# Bidirectional_Voltage_Translator.net
KiCad netlist of a schematic drawn in Altium Designer
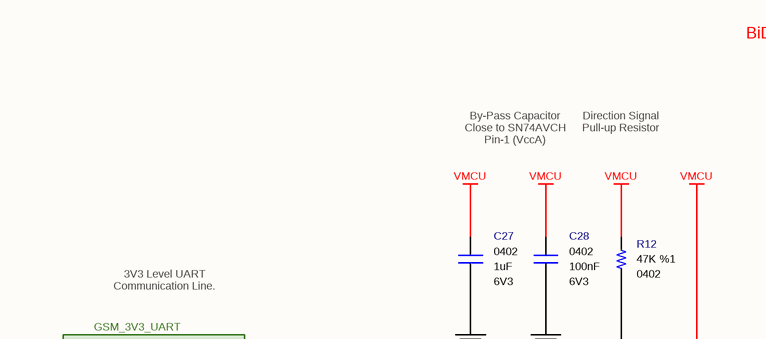
[diagram p0: Bidirectional Voltage Translator.SchDoc, top left]
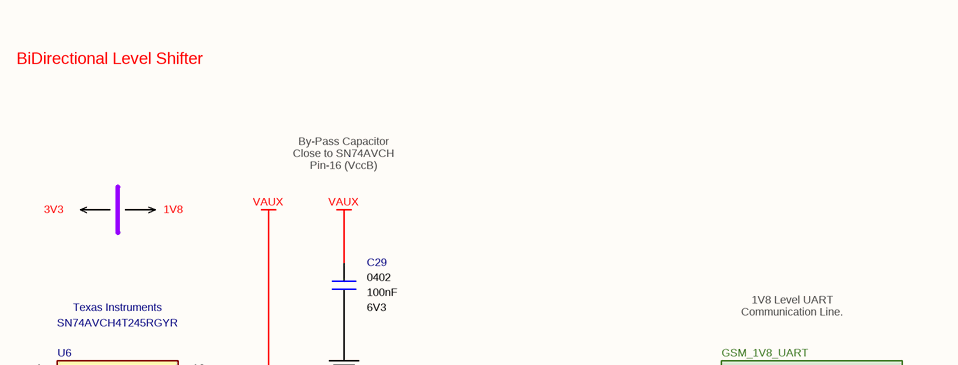
[diagram p1: Bidirectional Voltage Translator.SchDoc, top right]
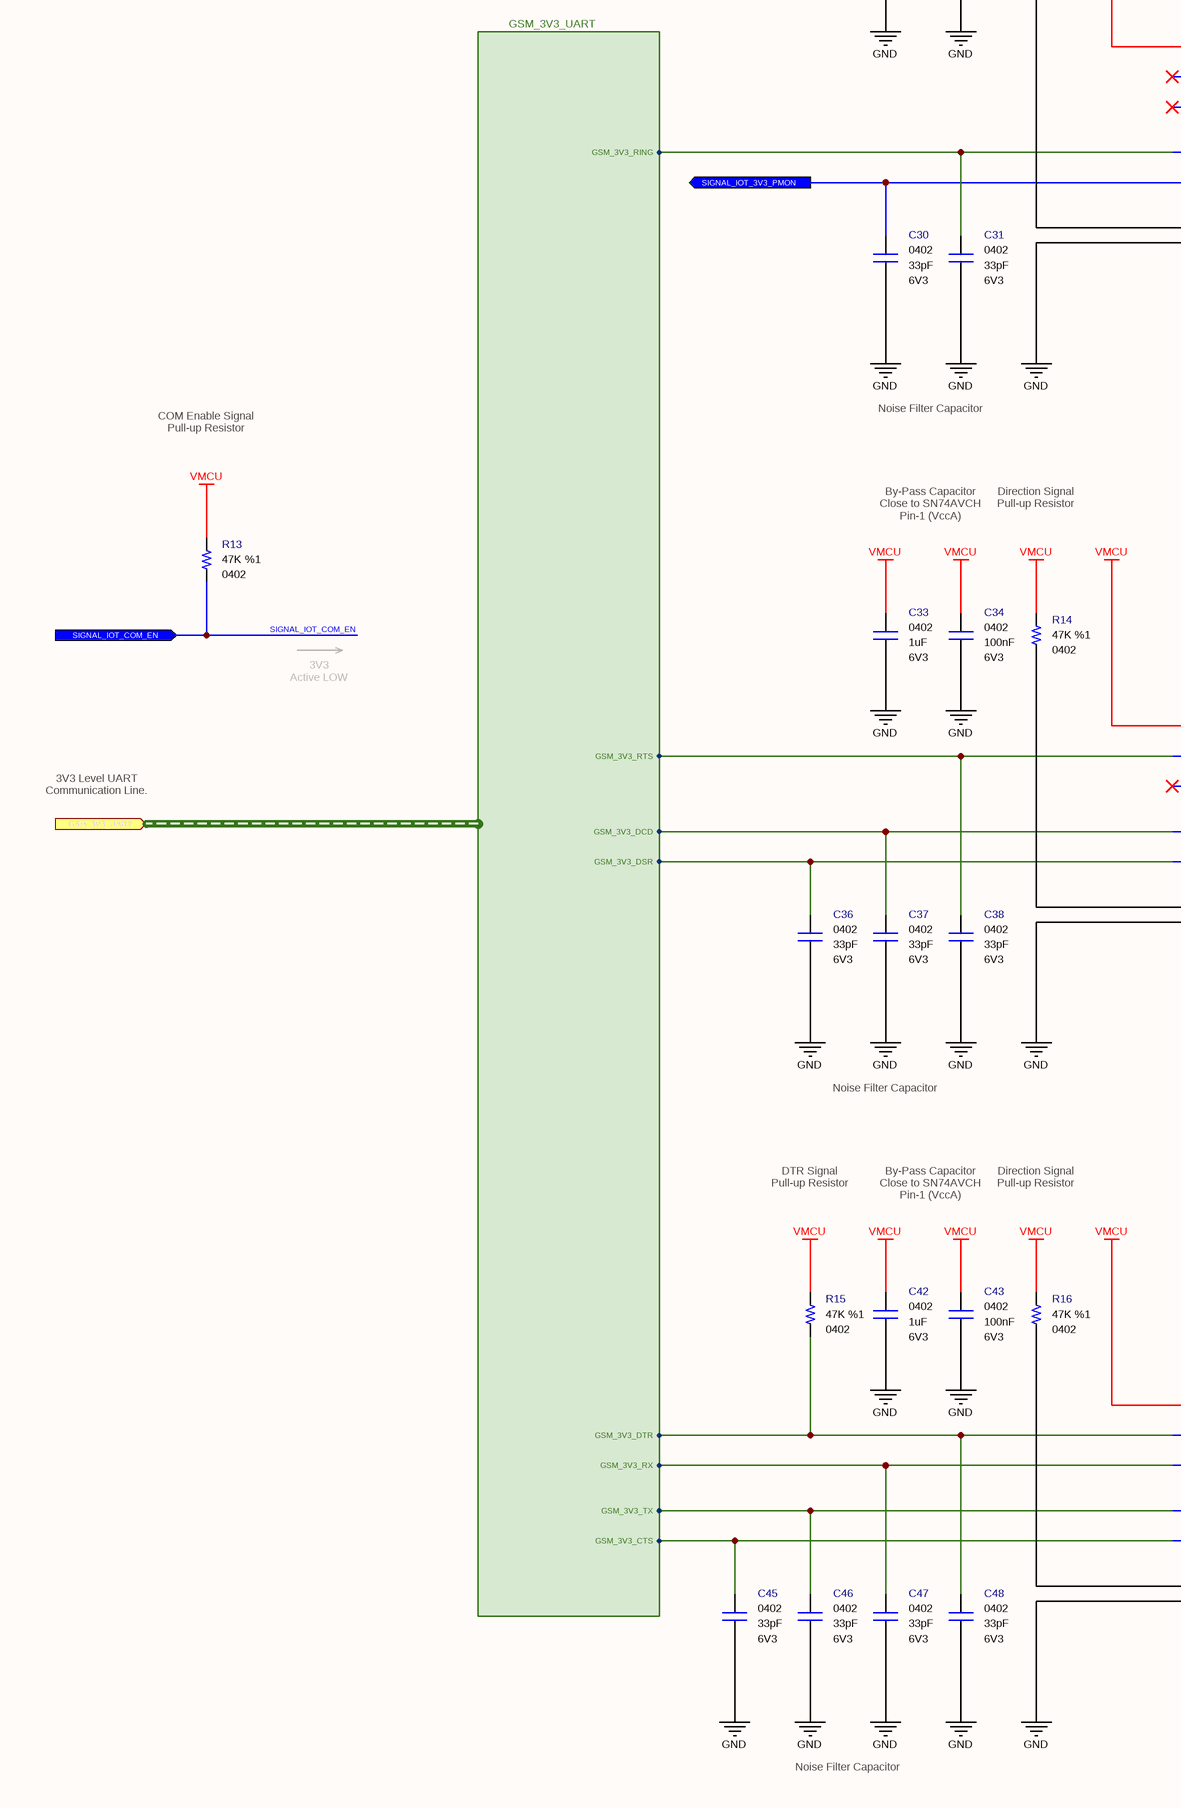
[diagram p2: Bidirectional Voltage Translator.SchDoc, bottom left]
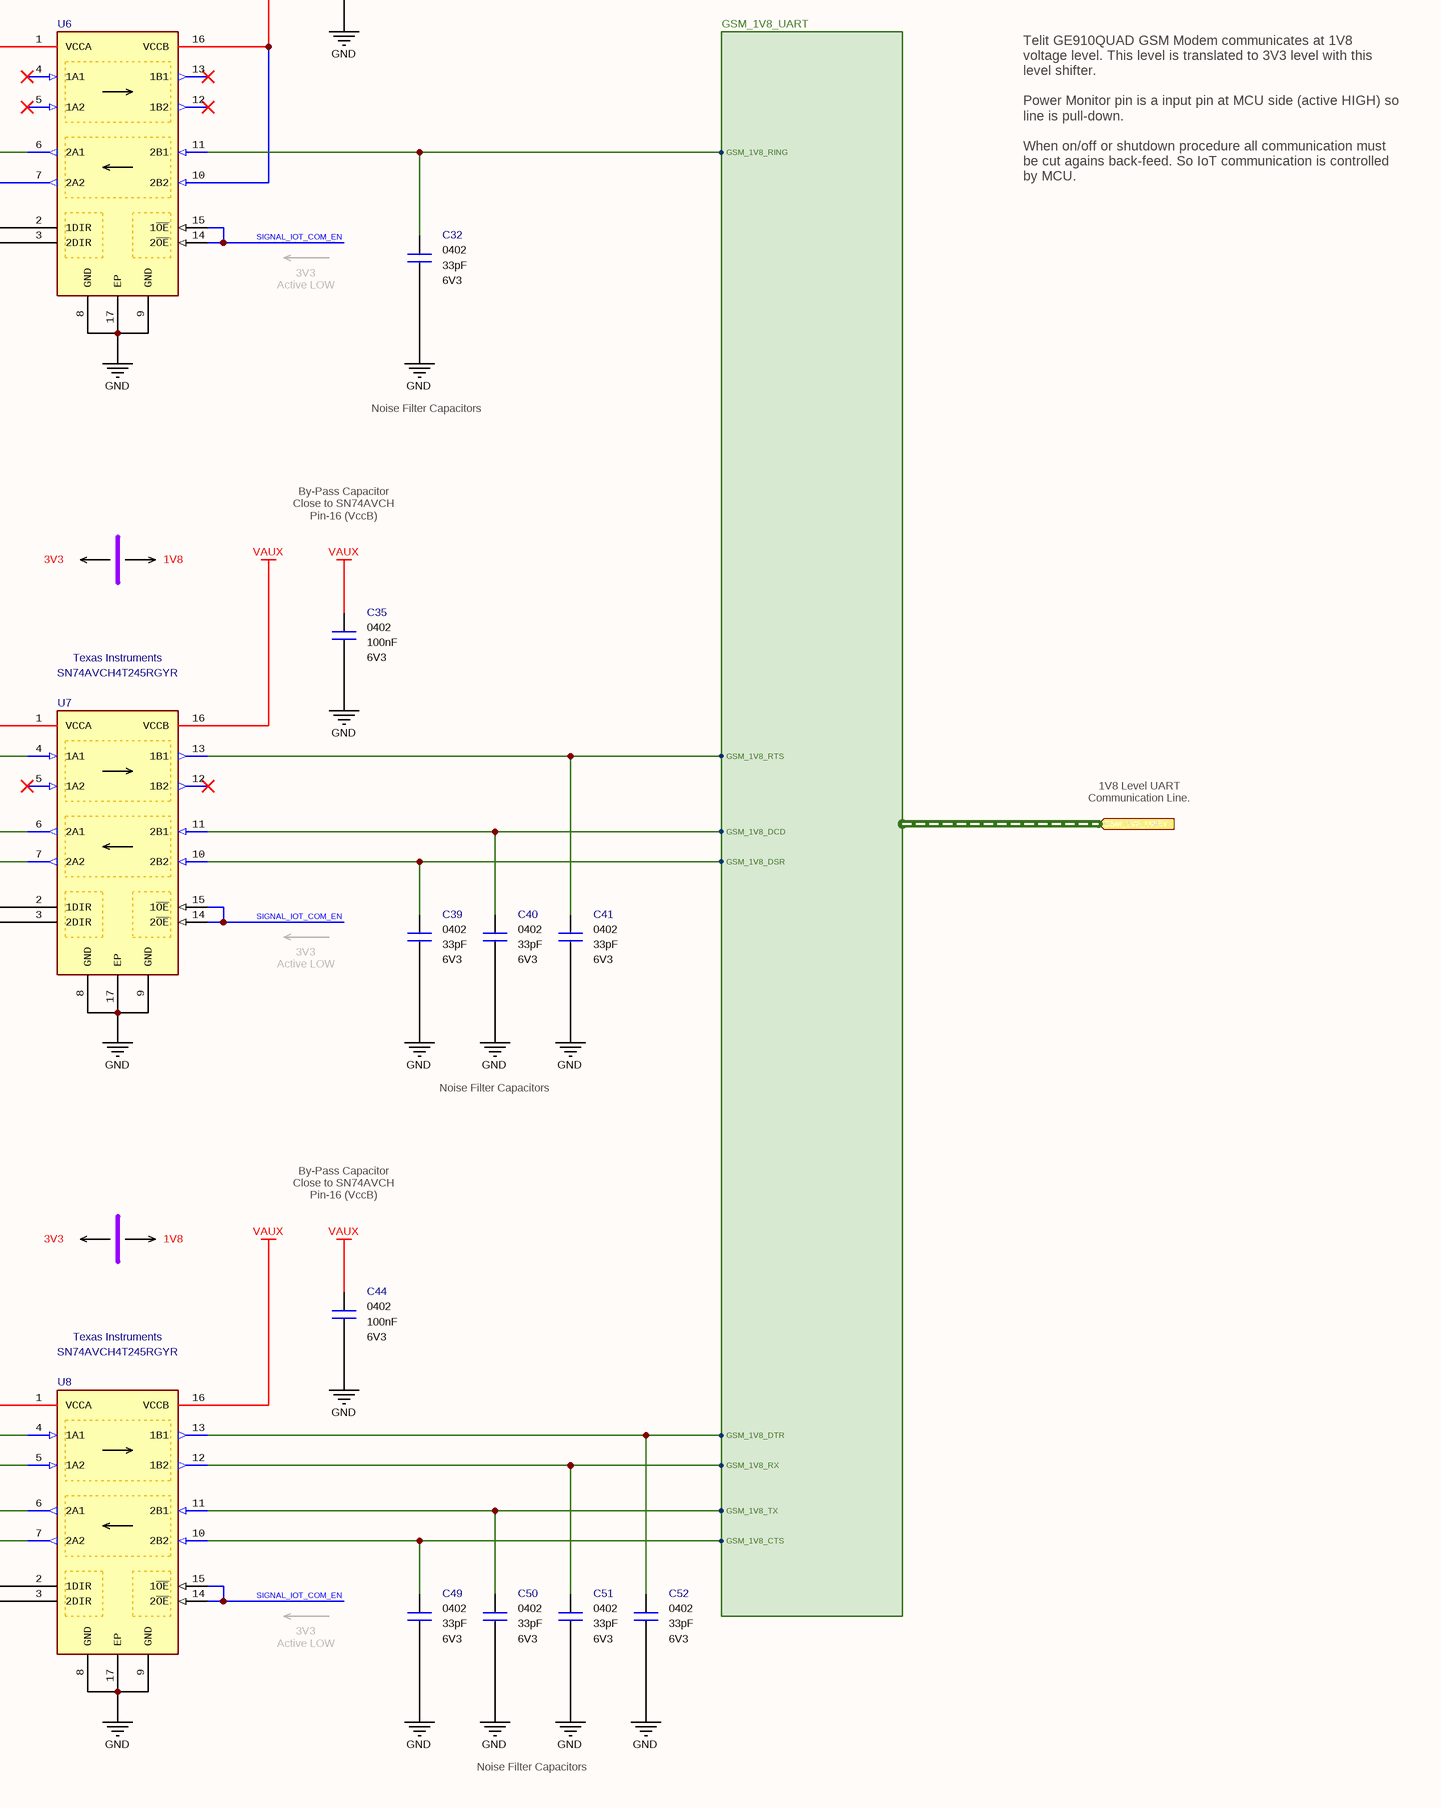
[diagram p3: Bidirectional Voltage Translator.SchDoc, bottom right]

(export (version "E")
  (design (tool "Eeschema 10.0.6"))
  (components
    (comp (ref "C27")
      (value "1uF")
      (footprint "CAPACITOR_0402")
      (description "Capacitor - 1uF [0402] (Ceramic)")
      (fields
        (field (name "TOLERANCE") "20%")
        (field (name "CASE") "0402")
        (field (name "VOLTAGE") "6V3")
        (field (name "MANUFACTURER PART NUMBER") "GRM153R60J105ME95D")
      )
      (libsource (lib "Ovoo_Library") (part "Capacitor - 1uF [0402-6V3]"))
    )
    (comp (ref "C28")
      (value "100nF")
      (footprint "CAPACITOR_0402")
      (description "Capacitor - 100nF [0402-6V3] (Ceramic)")
      (fields
        (field (name "TOLERANCE") "%10")
        (field (name "CASE") "0402")
        (field (name "VOLTAGE") "6V3")
        (field (name "MANUFACTURER PART NUMBER") "04026D104KAT4A")
      )
      (libsource (lib "Ovoo_Library") (part "Capacitor - 100nF [0402-6V3]"))
    )
    (comp (ref "C29")
      (value "100nF")
      (footprint "CAPACITOR_0402")
      (description "Capacitor - 100nF [0402-6V3] (Ceramic)")
      (fields
        (field (name "TOLERANCE") "%10")
        (field (name "CASE") "0402")
        (field (name "VOLTAGE") "6V3")
        (field (name "MANUFACTURER PART NUMBER") "04026D104KAT4A")
      )
      (libsource (lib "Ovoo_Library") (part "Capacitor - 100nF [0402-6V3]"))
    )
    (comp (ref "C30")
      (value "33pF")
      (footprint "CAPACITOR_0402")
      (description "Capacitor - 33pF [0402] (Ceramic)")
      (fields
        (field (name "TOLERANCE") "10%")
        (field (name "CASE") "0402")
        (field (name "VOLTAGE") "6V3")
        (field (name "MANUFACTURER PART NUMBER") "C0402C330J9RACAUTO")
      )
      (libsource (lib "Ovoo_Library") (part "Capacitor - 33pF [0402-6V3]"))
    )
    (comp (ref "C31")
      (value "33pF")
      (footprint "CAPACITOR_0402")
      (description "Capacitor - 33pF [0402] (Ceramic)")
      (fields
        (field (name "TOLERANCE") "10%")
        (field (name "CASE") "0402")
        (field (name "VOLTAGE") "6V3")
        (field (name "MANUFACTURER PART NUMBER") "C0402C330J9RACAUTO")
      )
      (libsource (lib "Ovoo_Library") (part "Capacitor - 33pF [0402-6V3]"))
    )
    (comp (ref "C32")
      (value "33pF")
      (footprint "CAPACITOR_0402")
      (description "Capacitor - 33pF [0402] (Ceramic)")
      (fields
        (field (name "TOLERANCE") "10%")
        (field (name "CASE") "0402")
        (field (name "VOLTAGE") "6V3")
        (field (name "MANUFACTURER PART NUMBER") "C0402C330J9RACAUTO")
      )
      (libsource (lib "Ovoo_Library") (part "Capacitor - 33pF [0402-6V3]"))
    )
    (comp (ref "C33")
      (value "1uF")
      (footprint "CAPACITOR_0402")
      (description "Capacitor - 1uF [0402] (Ceramic)")
      (fields
        (field (name "TOLERANCE") "20%")
        (field (name "CASE") "0402")
        (field (name "VOLTAGE") "6V3")
        (field (name "MANUFACTURER PART NUMBER") "GRM153R60J105ME95D")
      )
      (libsource (lib "Ovoo_Library") (part "Capacitor - 1uF [0402-6V3]"))
    )
    (comp (ref "C34")
      (value "100nF")
      (footprint "CAPACITOR_0402")
      (description "Capacitor - 100nF [0402-6V3] (Ceramic)")
      (fields
        (field (name "TOLERANCE") "%10")
        (field (name "CASE") "0402")
        (field (name "VOLTAGE") "6V3")
        (field (name "MANUFACTURER PART NUMBER") "04026D104KAT4A")
      )
      (libsource (lib "Ovoo_Library") (part "Capacitor - 100nF [0402-6V3]"))
    )
    (comp (ref "C35")
      (value "100nF")
      (footprint "CAPACITOR_0402")
      (description "Capacitor - 100nF [0402-6V3] (Ceramic)")
      (fields
        (field (name "TOLERANCE") "%10")
        (field (name "CASE") "0402")
        (field (name "VOLTAGE") "6V3")
        (field (name "MANUFACTURER PART NUMBER") "04026D104KAT4A")
      )
      (libsource (lib "Ovoo_Library") (part "Capacitor - 100nF [0402-6V3]"))
    )
    (comp (ref "C36")
      (value "33pF")
      (footprint "CAPACITOR_0402")
      (description "Capacitor - 33pF [0402] (Ceramic)")
      (fields
        (field (name "TOLERANCE") "10%")
        (field (name "CASE") "0402")
        (field (name "VOLTAGE") "6V3")
        (field (name "MANUFACTURER PART NUMBER") "C0402C330J9RACAUTO")
      )
      (libsource (lib "Ovoo_Library") (part "Capacitor - 33pF [0402-6V3]"))
    )
    (comp (ref "C37")
      (value "33pF")
      (footprint "CAPACITOR_0402")
      (description "Capacitor - 33pF [0402] (Ceramic)")
      (fields
        (field (name "TOLERANCE") "10%")
        (field (name "CASE") "0402")
        (field (name "VOLTAGE") "6V3")
        (field (name "MANUFACTURER PART NUMBER") "C0402C330J9RACAUTO")
      )
      (libsource (lib "Ovoo_Library") (part "Capacitor - 33pF [0402-6V3]"))
    )
    (comp (ref "C38")
      (value "33pF")
      (footprint "CAPACITOR_0402")
      (description "Capacitor - 33pF [0402] (Ceramic)")
      (fields
        (field (name "TOLERANCE") "10%")
        (field (name "CASE") "0402")
        (field (name "VOLTAGE") "6V3")
        (field (name "MANUFACTURER PART NUMBER") "C0402C330J9RACAUTO")
      )
      (libsource (lib "Ovoo_Library") (part "Capacitor - 33pF [0402-6V3]"))
    )
    (comp (ref "C39")
      (value "33pF")
      (footprint "CAPACITOR_0402")
      (description "Capacitor - 33pF [0402] (Ceramic)")
      (fields
        (field (name "TOLERANCE") "10%")
        (field (name "CASE") "0402")
        (field (name "VOLTAGE") "6V3")
        (field (name "MANUFACTURER PART NUMBER") "C0402C330J9RACAUTO")
      )
      (libsource (lib "Ovoo_Library") (part "Capacitor - 33pF [0402-6V3]"))
    )
    (comp (ref "C40")
      (value "33pF")
      (footprint "CAPACITOR_0402")
      (description "Capacitor - 33pF [0402] (Ceramic)")
      (fields
        (field (name "TOLERANCE") "10%")
        (field (name "CASE") "0402")
        (field (name "VOLTAGE") "6V3")
        (field (name "MANUFACTURER PART NUMBER") "C0402C330J9RACAUTO")
      )
      (libsource (lib "Ovoo_Library") (part "Capacitor - 33pF [0402-6V3]"))
    )
    (comp (ref "C41")
      (value "33pF")
      (footprint "CAPACITOR_0402")
      (description "Capacitor - 33pF [0402] (Ceramic)")
      (fields
        (field (name "TOLERANCE") "10%")
        (field (name "CASE") "0402")
        (field (name "VOLTAGE") "6V3")
        (field (name "MANUFACTURER PART NUMBER") "C0402C330J9RACAUTO")
      )
      (libsource (lib "Ovoo_Library") (part "Capacitor - 33pF [0402-6V3]"))
    )
    (comp (ref "C42")
      (value "1uF")
      (footprint "CAPACITOR_0402")
      (description "Capacitor - 1uF [0402] (Ceramic)")
      (fields
        (field (name "TOLERANCE") "20%")
        (field (name "CASE") "0402")
        (field (name "VOLTAGE") "6V3")
        (field (name "MANUFACTURER PART NUMBER") "GRM153R60J105ME95D")
      )
      (libsource (lib "Ovoo_Library") (part "Capacitor - 1uF [0402-6V3]"))
    )
    (comp (ref "C43")
      (value "100nF")
      (footprint "CAPACITOR_0402")
      (description "Capacitor - 100nF [0402-6V3] (Ceramic)")
      (fields
        (field (name "TOLERANCE") "%10")
        (field (name "CASE") "0402")
        (field (name "VOLTAGE") "6V3")
        (field (name "MANUFACTURER PART NUMBER") "04026D104KAT4A")
      )
      (libsource (lib "Ovoo_Library") (part "Capacitor - 100nF [0402-6V3]"))
    )
    (comp (ref "C44")
      (value "100nF")
      (footprint "CAPACITOR_0402")
      (description "Capacitor - 100nF [0402-6V3] (Ceramic)")
      (fields
        (field (name "TOLERANCE") "%10")
        (field (name "CASE") "0402")
        (field (name "VOLTAGE") "6V3")
        (field (name "MANUFACTURER PART NUMBER") "04026D104KAT4A")
      )
      (libsource (lib "Ovoo_Library") (part "Capacitor - 100nF [0402-6V3]"))
    )
    (comp (ref "C45")
      (value "33pF")
      (footprint "CAPACITOR_0402")
      (description "Capacitor - 33pF [0402] (Ceramic)")
      (fields
        (field (name "TOLERANCE") "10%")
        (field (name "CASE") "0402")
        (field (name "VOLTAGE") "6V3")
        (field (name "MANUFACTURER PART NUMBER") "C0402C330J9RACAUTO")
      )
      (libsource (lib "Ovoo_Library") (part "Capacitor - 33pF [0402-6V3]"))
    )
    (comp (ref "C46")
      (value "33pF")
      (footprint "CAPACITOR_0402")
      (description "Capacitor - 33pF [0402] (Ceramic)")
      (fields
        (field (name "TOLERANCE") "10%")
        (field (name "CASE") "0402")
        (field (name "VOLTAGE") "6V3")
        (field (name "MANUFACTURER PART NUMBER") "C0402C330J9RACAUTO")
      )
      (libsource (lib "Ovoo_Library") (part "Capacitor - 33pF [0402-6V3]"))
    )
    (comp (ref "C47")
      (value "33pF")
      (footprint "CAPACITOR_0402")
      (description "Capacitor - 33pF [0402] (Ceramic)")
      (fields
        (field (name "TOLERANCE") "10%")
        (field (name "CASE") "0402")
        (field (name "VOLTAGE") "6V3")
        (field (name "MANUFACTURER PART NUMBER") "C0402C330J9RACAUTO")
      )
      (libsource (lib "Ovoo_Library") (part "Capacitor - 33pF [0402-6V3]"))
    )
    (comp (ref "C48")
      (value "33pF")
      (footprint "CAPACITOR_0402")
      (description "Capacitor - 33pF [0402] (Ceramic)")
      (fields
        (field (name "TOLERANCE") "10%")
        (field (name "CASE") "0402")
        (field (name "VOLTAGE") "6V3")
        (field (name "MANUFACTURER PART NUMBER") "C0402C330J9RACAUTO")
      )
      (libsource (lib "Ovoo_Library") (part "Capacitor - 33pF [0402-6V3]"))
    )
    (comp (ref "C49")
      (value "33pF")
      (footprint "CAPACITOR_0402")
      (description "Capacitor - 33pF [0402] (Ceramic)")
      (fields
        (field (name "TOLERANCE") "10%")
        (field (name "CASE") "0402")
        (field (name "VOLTAGE") "6V3")
        (field (name "MANUFACTURER PART NUMBER") "C0402C330J9RACAUTO")
      )
      (libsource (lib "Ovoo_Library") (part "Capacitor - 33pF [0402-6V3]"))
    )
    (comp (ref "C50")
      (value "33pF")
      (footprint "CAPACITOR_0402")
      (description "Capacitor - 33pF [0402] (Ceramic)")
      (fields
        (field (name "TOLERANCE") "10%")
        (field (name "CASE") "0402")
        (field (name "VOLTAGE") "6V3")
        (field (name "MANUFACTURER PART NUMBER") "C0402C330J9RACAUTO")
      )
      (libsource (lib "Ovoo_Library") (part "Capacitor - 33pF [0402-6V3]"))
    )
    (comp (ref "C51")
      (value "33pF")
      (footprint "CAPACITOR_0402")
      (description "Capacitor - 33pF [0402] (Ceramic)")
      (fields
        (field (name "TOLERANCE") "10%")
        (field (name "CASE") "0402")
        (field (name "VOLTAGE") "6V3")
        (field (name "MANUFACTURER PART NUMBER") "C0402C330J9RACAUTO")
      )
      (libsource (lib "Ovoo_Library") (part "Capacitor - 33pF [0402-6V3]"))
    )
    (comp (ref "C52")
      (value "33pF")
      (footprint "CAPACITOR_0402")
      (description "Capacitor - 33pF [0402] (Ceramic)")
      (fields
        (field (name "TOLERANCE") "10%")
        (field (name "CASE") "0402")
        (field (name "VOLTAGE") "6V3")
        (field (name "MANUFACTURER PART NUMBER") "C0402C330J9RACAUTO")
      )
      (libsource (lib "Ovoo_Library") (part "Capacitor - 33pF [0402-6V3]"))
    )
    (comp (ref "R12")
      (value "47K")
      (footprint "RESISTOR_0402")
      (description "Thick Film Resistors - SMD 1/16 W 47 Kohms 1%")
      (fields
        (field (name "TOLERANCE") "%1")
        (field (name "CASE") "0402")
        (field (name "MANUFACTURER PART NUMBER") "CRCW040247K0FKED")
        (field (name "Comment") "47K - 0402 - %1 - 1/16W")
      )
      (libsource (lib "Ovoo_Library") (part "Resistor - 47K"))
    )
    (comp (ref "R13")
      (value "47K")
      (footprint "RESISTOR_0402")
      (description "Thick Film Resistors - SMD 1/16 W 47 Kohms 1%")
      (fields
        (field (name "TOLERANCE") "%1")
        (field (name "CASE") "0402")
        (field (name "MANUFACTURER PART NUMBER") "CRCW040247K0FKED")
        (field (name "Comment") "47K - 0402 - %1 - 1/16W")
      )
      (libsource (lib "Ovoo_Library") (part "Resistor - 47K"))
    )
    (comp (ref "R14")
      (value "47K")
      (footprint "RESISTOR_0402")
      (description "Thick Film Resistors - SMD 1/16 W 47 Kohms 1%")
      (fields
        (field (name "TOLERANCE") "%1")
        (field (name "CASE") "0402")
        (field (name "MANUFACTURER PART NUMBER") "CRCW040247K0FKED")
        (field (name "Comment") "47K - 0402 - %1 - 1/16W")
      )
      (libsource (lib "Ovoo_Library") (part "Resistor - 47K"))
    )
    (comp (ref "R15")
      (value "47K")
      (footprint "RESISTOR_0402")
      (description "Thick Film Resistors - SMD 1/16 W 47 Kohms 1%")
      (fields
        (field (name "TOLERANCE") "%1")
        (field (name "CASE") "0402")
        (field (name "MANUFACTURER PART NUMBER") "CRCW040247K0FKED")
        (field (name "Comment") "47K - 0402 - %1 - 1/16W")
      )
      (libsource (lib "Ovoo_Library") (part "Resistor - 47K"))
    )
    (comp (ref "R16")
      (value "47K")
      (footprint "RESISTOR_0402")
      (description "Thick Film Resistors - SMD 1/16 W 47 Kohms 1%")
      (fields
        (field (name "TOLERANCE") "%1")
        (field (name "CASE") "0402")
        (field (name "MANUFACTURER PART NUMBER") "CRCW040247K0FKED")
        (field (name "Comment") "47K - 0402 - %1 - 1/16W")
      )
      (libsource (lib "Ovoo_Library") (part "Resistor - 47K"))
    )
    (comp (ref "U6")
      (value "Voltage Level Shifter")
      (footprint "VQFN16")
      (description "Translation - Voltage Levels Low Power Dual Channel")
      (fields
        (field (name "MOUSER PART NUMBER") "595-SN74AVCH4T245RGY")
        (field (name "MANUFACTURER PART NUMBER") "SN74AVCH4T245RGYR")
        (field (name "MANUFACTURER NAME") "Texas Instruments")
      )
      (libsource (lib "Ovoo_Library") (part "IC - SN74AVCH4T245"))
    )
    (comp (ref "U7")
      (value "Voltage Level Shifter")
      (footprint "VQFN16")
      (description "Translation - Voltage Levels Low Power Dual Channel")
      (fields
        (field (name "MOUSER PART NUMBER") "595-SN74AVCH4T245RGY")
        (field (name "MANUFACTURER PART NUMBER") "SN74AVCH4T245RGYR")
        (field (name "MANUFACTURER NAME") "Texas Instruments")
      )
      (libsource (lib "Ovoo_Library") (part "IC - SN74AVCH4T245"))
    )
    (comp (ref "U8")
      (value "Voltage Level Shifter")
      (footprint "VQFN16")
      (description "Translation - Voltage Levels Low Power Dual Channel")
      (fields
        (field (name "MOUSER PART NUMBER") "595-SN74AVCH4T245RGY")
        (field (name "MANUFACTURER PART NUMBER") "SN74AVCH4T245RGYR")
        (field (name "MANUFACTURER NAME") "Texas Instruments")
      )
      (libsource (lib "Ovoo_Library") (part "IC - SN74AVCH4T245"))
    )
  )
  (nets
    (net (code "3") (name "/SIGNAL_IOT_3V3_PMON") (class "Default")
      (node (ref "C30") (pin "2") (pinfunction "2_2") (pintype "passive"))
      (node (ref "U6") (pin "7") (pinfunction "2A2_7") (pintype "output"))
    )
    (net (code "4") (name "/SIGNAL_IOT_COM_EN") (class "Default")
      (node (ref "R13") (pin "1") (pinfunction "1_1") (pintype "passive"))
      (node (ref "U6") (pin "14") (pinfunction "2~{OE}_14") (pintype "input"))
      (node (ref "U6") (pin "15") (pinfunction "1~{OE}_15") (pintype "input"))
      (node (ref "U7") (pin "14") (pinfunction "2~{OE}_14") (pintype "input"))
      (node (ref "U7") (pin "15") (pinfunction "1~{OE}_15") (pintype "input"))
      (node (ref "U8") (pin "14") (pinfunction "2~{OE}_14") (pintype "input"))
      (node (ref "U8") (pin "15") (pinfunction "1~{OE}_15") (pintype "input"))
    )
    (net (code "7") (name "GND") (class "Default")
      (node (ref "C27") (pin "1") (pinfunction "1_1") (pintype "passive"))
      (node (ref "C28") (pin "1") (pinfunction "1_1") (pintype "passive"))
      (node (ref "C29") (pin "1") (pinfunction "1_1") (pintype "passive"))
      (node (ref "C30") (pin "1") (pinfunction "1_1") (pintype "passive"))
      (node (ref "C31") (pin "1") (pinfunction "1_1") (pintype "passive"))
      (node (ref "C32") (pin "1") (pinfunction "1_1") (pintype "passive"))
      (node (ref "C33") (pin "1") (pinfunction "1_1") (pintype "passive"))
      (node (ref "C34") (pin "1") (pinfunction "1_1") (pintype "passive"))
      (node (ref "C35") (pin "1") (pinfunction "1_1") (pintype "passive"))
      (node (ref "C36") (pin "1") (pinfunction "1_1") (pintype "passive"))
      (node (ref "C37") (pin "1") (pinfunction "1_1") (pintype "passive"))
      (node (ref "C38") (pin "1") (pinfunction "1_1") (pintype "passive"))
      (node (ref "C39") (pin "1") (pinfunction "1_1") (pintype "passive"))
      (node (ref "C40") (pin "1") (pinfunction "1_1") (pintype "passive"))
      (node (ref "C41") (pin "1") (pinfunction "1_1") (pintype "passive"))
      (node (ref "C42") (pin "1") (pinfunction "1_1") (pintype "passive"))
      (node (ref "C43") (pin "1") (pinfunction "1_1") (pintype "passive"))
      (node (ref "C44") (pin "1") (pinfunction "1_1") (pintype "passive"))
      (node (ref "C45") (pin "1") (pinfunction "1_1") (pintype "passive"))
      (node (ref "C46") (pin "1") (pinfunction "1_1") (pintype "passive"))
      (node (ref "C47") (pin "1") (pinfunction "1_1") (pintype "passive"))
      (node (ref "C48") (pin "1") (pinfunction "1_1") (pintype "passive"))
      (node (ref "C49") (pin "1") (pinfunction "1_1") (pintype "passive"))
      (node (ref "C50") (pin "1") (pinfunction "1_1") (pintype "passive"))
      (node (ref "C51") (pin "1") (pinfunction "1_1") (pintype "passive"))
      (node (ref "C52") (pin "1") (pinfunction "1_1") (pintype "passive"))
      (node (ref "U6") (pin "17") (pinfunction "EP_17") (pintype "power_in"))
      (node (ref "U6") (pin "3") (pinfunction "2DIR_3") (pintype "passive"))
      (node (ref "U6") (pin "8") (pinfunction "GND_8") (pintype "power_in"))
      (node (ref "U6") (pin "9") (pinfunction "GND_9") (pintype "power_in"))
      (node (ref "U7") (pin "17") (pinfunction "EP_17") (pintype "power_in"))
      (node (ref "U7") (pin "3") (pinfunction "2DIR_3") (pintype "passive"))
      (node (ref "U7") (pin "8") (pinfunction "GND_8") (pintype "power_in"))
      (node (ref "U7") (pin "9") (pinfunction "GND_9") (pintype "power_in"))
      (node (ref "U8") (pin "17") (pinfunction "EP_17") (pintype "power_in"))
      (node (ref "U8") (pin "3") (pinfunction "2DIR_3") (pintype "passive"))
      (node (ref "U8") (pin "8") (pinfunction "GND_8") (pintype "power_in"))
      (node (ref "U8") (pin "9") (pinfunction "GND_9") (pintype "power_in"))
    )
    (net (code "8") (name "Net-(U6-1DIR)") (class "Default")
      (node (ref "R12") (pin "1") (pinfunction "1_1") (pintype "passive"))
      (node (ref "U6") (pin "2") (pinfunction "1DIR_2") (pintype "passive"))
    )
    (net (code "9") (name "Net-(U6-2A1)") (class "Default")
      (node (ref "C31") (pin "2") (pinfunction "2_2") (pintype "passive"))
      (node (ref "U6") (pin "6") (pinfunction "2A1_6") (pintype "output"))
    )
    (net (code "10") (name "Net-(U6-2B1)") (class "Default")
      (node (ref "C32") (pin "2") (pinfunction "2_2") (pintype "passive"))
      (node (ref "U6") (pin "11") (pinfunction "2B1_11") (pintype "input"))
    )
    (net (code "11") (name "Net-(U7-1A1)") (class "Default")
      (node (ref "C38") (pin "2") (pinfunction "2_2") (pintype "passive"))
      (node (ref "U7") (pin "4") (pinfunction "1A1_4") (pintype "input"))
    )
    (net (code "12") (name "Net-(U7-1B1)") (class "Default")
      (node (ref "C41") (pin "2") (pinfunction "2_2") (pintype "passive"))
      (node (ref "U7") (pin "13") (pinfunction "1B1_13") (pintype "output"))
    )
    (net (code "13") (name "Net-(U7-1DIR)") (class "Default")
      (node (ref "R14") (pin "1") (pinfunction "1_1") (pintype "passive"))
      (node (ref "U7") (pin "2") (pinfunction "1DIR_2") (pintype "passive"))
    )
    (net (code "14") (name "Net-(U7-2A1)") (class "Default")
      (node (ref "C37") (pin "2") (pinfunction "2_2") (pintype "passive"))
      (node (ref "U7") (pin "6") (pinfunction "2A1_6") (pintype "output"))
    )
    (net (code "15") (name "Net-(U7-2A2)") (class "Default")
      (node (ref "C36") (pin "2") (pinfunction "2_2") (pintype "passive"))
      (node (ref "U7") (pin "7") (pinfunction "2A2_7") (pintype "output"))
    )
    (net (code "16") (name "Net-(U7-2B1)") (class "Default")
      (node (ref "C40") (pin "2") (pinfunction "2_2") (pintype "passive"))
      (node (ref "U7") (pin "11") (pinfunction "2B1_11") (pintype "input"))
    )
    (net (code "17") (name "Net-(U7-2B2)") (class "Default")
      (node (ref "C39") (pin "2") (pinfunction "2_2") (pintype "passive"))
      (node (ref "U7") (pin "10") (pinfunction "2B2_10") (pintype "input"))
    )
    (net (code "18") (name "Net-(U8-1A1)") (class "Default")
      (node (ref "C48") (pin "2") (pinfunction "2_2") (pintype "passive"))
      (node (ref "R15") (pin "1") (pinfunction "1_1") (pintype "passive"))
      (node (ref "U8") (pin "4") (pinfunction "1A1_4") (pintype "input"))
    )
    (net (code "19") (name "Net-(U8-1A2)") (class "Default")
      (node (ref "C47") (pin "2") (pinfunction "2_2") (pintype "passive"))
      (node (ref "U8") (pin "5") (pinfunction "1A2_5") (pintype "input"))
    )
    (net (code "20") (name "Net-(U8-1B1)") (class "Default")
      (node (ref "C52") (pin "2") (pinfunction "2_2") (pintype "passive"))
      (node (ref "U8") (pin "13") (pinfunction "1B1_13") (pintype "output"))
    )
    (net (code "21") (name "Net-(U8-1B2)") (class "Default")
      (node (ref "C51") (pin "2") (pinfunction "2_2") (pintype "passive"))
      (node (ref "U8") (pin "12") (pinfunction "1B2_12") (pintype "output"))
    )
    (net (code "22") (name "Net-(U8-1DIR)") (class "Default")
      (node (ref "R16") (pin "1") (pinfunction "1_1") (pintype "passive"))
      (node (ref "U8") (pin "2") (pinfunction "1DIR_2") (pintype "passive"))
    )
    (net (code "23") (name "Net-(U8-2A1)") (class "Default")
      (node (ref "C46") (pin "2") (pinfunction "2_2") (pintype "passive"))
      (node (ref "U8") (pin "6") (pinfunction "2A1_6") (pintype "output"))
    )
    (net (code "24") (name "Net-(U8-2A2)") (class "Default")
      (node (ref "C45") (pin "2") (pinfunction "2_2") (pintype "passive"))
      (node (ref "U8") (pin "7") (pinfunction "2A2_7") (pintype "output"))
    )
    (net (code "25") (name "Net-(U8-2B1)") (class "Default")
      (node (ref "C50") (pin "2") (pinfunction "2_2") (pintype "passive"))
      (node (ref "U8") (pin "11") (pinfunction "2B1_11") (pintype "input"))
    )
    (net (code "26") (name "Net-(U8-2B2)") (class "Default")
      (node (ref "C49") (pin "2") (pinfunction "2_2") (pintype "passive"))
      (node (ref "U8") (pin "10") (pinfunction "2B2_10") (pintype "input"))
    )
    (net (code "27") (name "VAUX") (class "Default")
      (node (ref "C29") (pin "2") (pinfunction "2_2") (pintype "passive"))
      (node (ref "C35") (pin "2") (pinfunction "2_2") (pintype "passive"))
      (node (ref "C44") (pin "2") (pinfunction "2_2") (pintype "passive"))
      (node (ref "U6") (pin "10") (pinfunction "2B2_10") (pintype "input"))
      (node (ref "U6") (pin "16") (pinfunction "VCCB_16") (pintype "power_in"))
      (node (ref "U7") (pin "16") (pinfunction "VCCB_16") (pintype "power_in"))
      (node (ref "U8") (pin "16") (pinfunction "VCCB_16") (pintype "power_in"))
    )
    (net (code "28") (name "VMCU") (class "Default")
      (node (ref "C27") (pin "2") (pinfunction "2_2") (pintype "passive"))
      (node (ref "C28") (pin "2") (pinfunction "2_2") (pintype "passive"))
      (node (ref "C33") (pin "2") (pinfunction "2_2") (pintype "passive"))
      (node (ref "C34") (pin "2") (pinfunction "2_2") (pintype "passive"))
      (node (ref "C42") (pin "2") (pinfunction "2_2") (pintype "passive"))
      (node (ref "C43") (pin "2") (pinfunction "2_2") (pintype "passive"))
      (node (ref "R12") (pin "2") (pinfunction "2_2") (pintype "passive"))
      (node (ref "R13") (pin "2") (pinfunction "2_2") (pintype "passive"))
      (node (ref "R14") (pin "2") (pinfunction "2_2") (pintype "passive"))
      (node (ref "R15") (pin "2") (pinfunction "2_2") (pintype "passive"))
      (node (ref "R16") (pin "2") (pinfunction "2_2") (pintype "passive"))
      (node (ref "U6") (pin "1") (pinfunction "VCCA_1") (pintype "power_in"))
      (node (ref "U7") (pin "1") (pinfunction "VCCA_1") (pintype "power_in"))
      (node (ref "U8") (pin "1") (pinfunction "VCCA_1") (pintype "power_in"))
    )
    (net (code "29") (name "unconnected-(U6-1A1-Pad4)") (class "Default")
      (node (ref "U6") (pin "4") (pinfunction "1A1_4") (pintype "input+no_connect"))
    )
    (net (code "30") (name "unconnected-(U6-1A2-Pad5)") (class "Default")
      (node (ref "U6") (pin "5") (pinfunction "1A2_5") (pintype "input+no_connect"))
    )
    (net (code "31") (name "unconnected-(U6-1B1-Pad13)") (class "Default")
      (node (ref "U6") (pin "13") (pinfunction "1B1_13") (pintype "output+no_connect"))
    )
    (net (code "32") (name "unconnected-(U6-1B2-Pad12)") (class "Default")
      (node (ref "U6") (pin "12") (pinfunction "1B2_12") (pintype "output+no_connect"))
    )
    (net (code "33") (name "unconnected-(U7-1A2-Pad5)") (class "Default")
      (node (ref "U7") (pin "5") (pinfunction "1A2_5") (pintype "input+no_connect"))
    )
    (net (code "34") (name "unconnected-(U7-1B2-Pad12)") (class "Default")
      (node (ref "U7") (pin "12") (pinfunction "1B2_12") (pintype "output+no_connect"))
    )
  )
)
